# Arduino_car.net
KiCad netlist of a schematic drawn in EAGLE
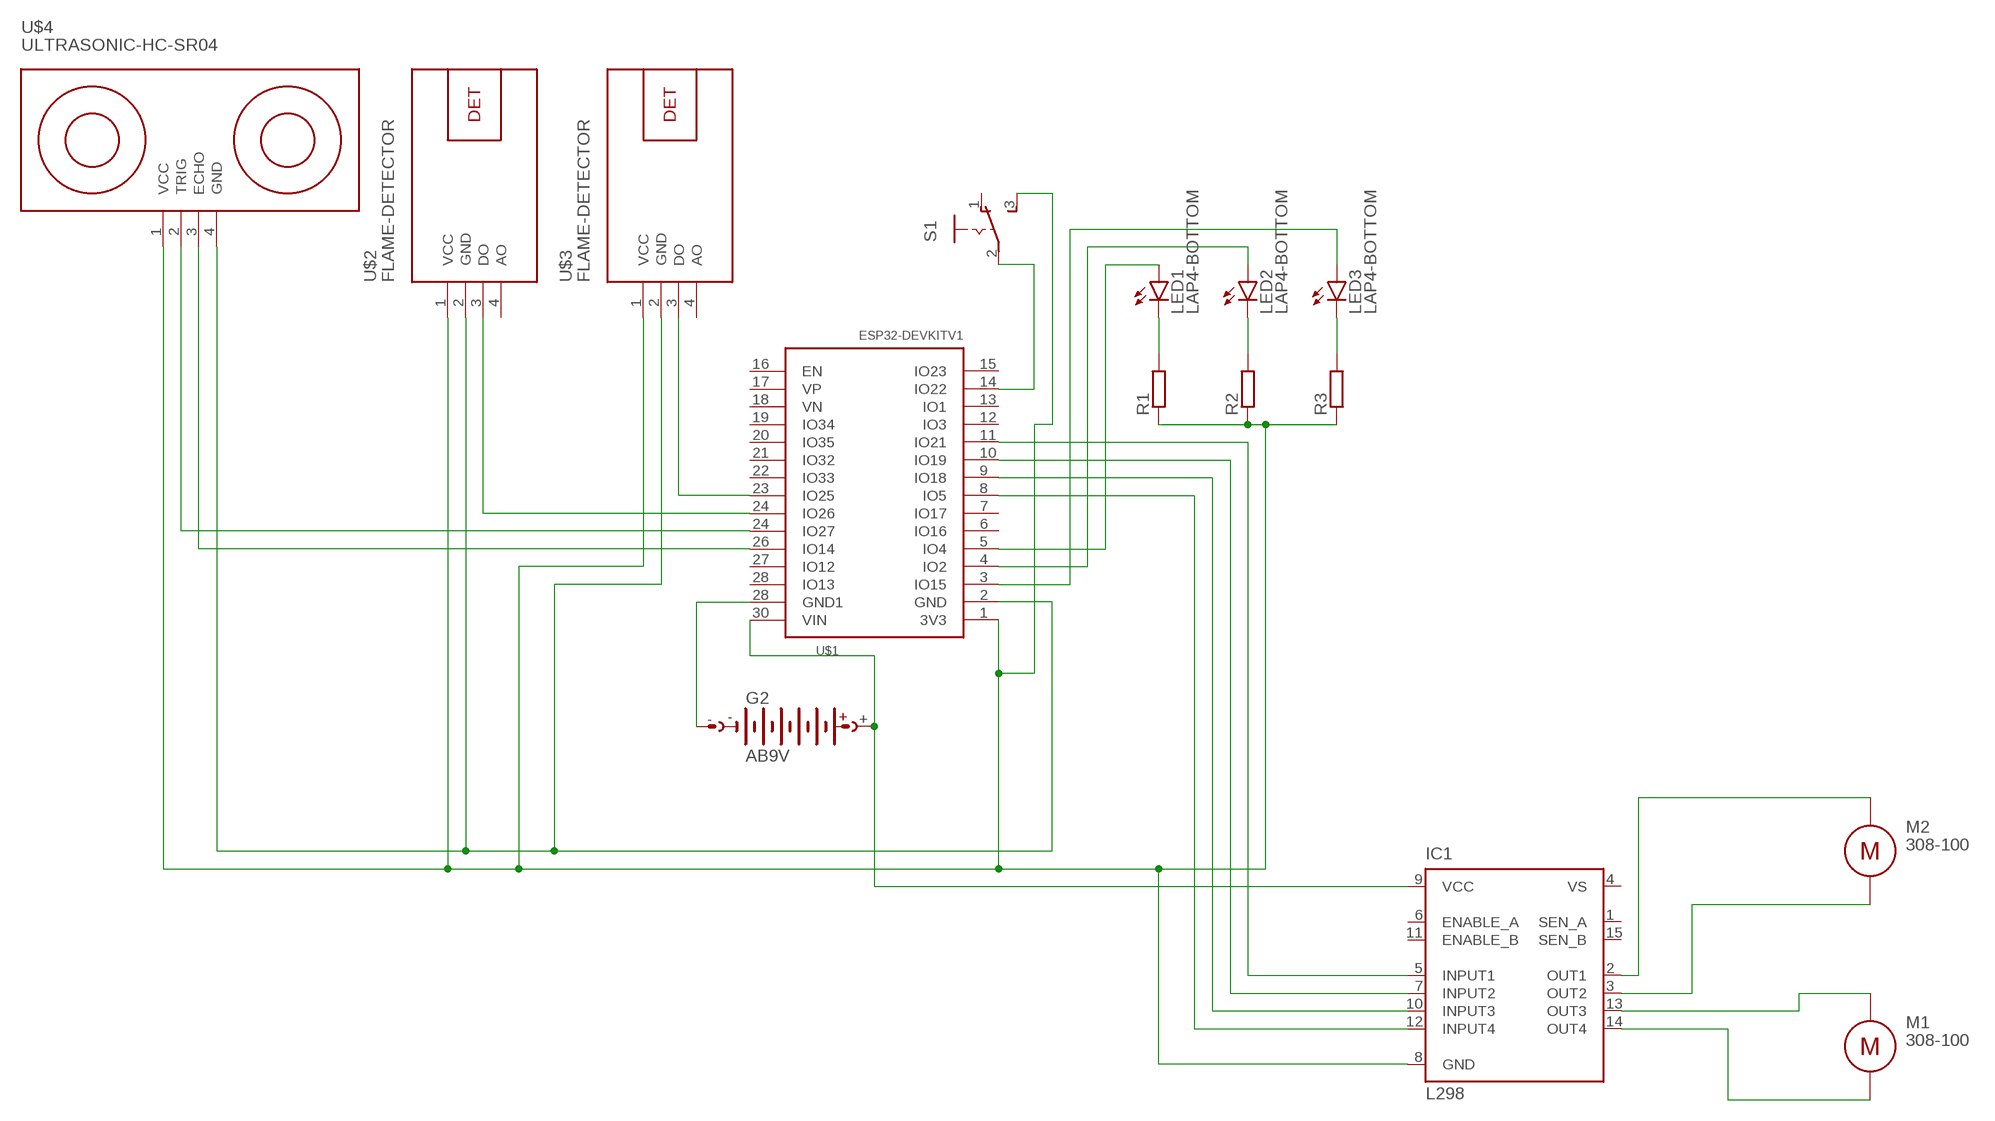
[diagram p0: schematic, sheet 1]

(export (version "E")
  (design (tool "Eeschema 10.0.6"))
  (components
    (comp (ref "G2")
      (value "AB9V")
      (footprint "eagle-import:AB9V")
      (libsource (lib "eagle-import") (part "AB9V"))
    )
    (comp (ref "IC1")
      (value "L298")
      (footprint "eagle-import:MULTIWATT-15")
      (libsource (lib "eagle-import") (part "L298"))
    )
    (comp (ref "LED1")
      (value "LAP4-BOTTOM")
      (footprint "eagle-import:P47F-BOTTOM")
      (libsource (lib "eagle-import") (part "P4-BOTTOMLA"))
    )
    (comp (ref "LED2")
      (value "LAP4-BOTTOM")
      (footprint "eagle-import:P47F-BOTTOM")
      (libsource (lib "eagle-import") (part "P4-BOTTOMLA"))
    )
    (comp (ref "LED3")
      (value "LAP4-BOTTOM")
      (footprint "eagle-import:P47F-BOTTOM")
      (libsource (lib "eagle-import") (part "P4-BOTTOMLA"))
    )
    (comp (ref "M1")
      (value "308-100")
      (footprint "eagle-import:308-100")
      (libsource (lib "eagle-import") (part "308-100"))
    )
    (comp (ref "M2")
      (value "308-100")
      (footprint "eagle-import:308-100")
      (libsource (lib "eagle-import") (part "308-100"))
    )
    (comp (ref "R1")
      (value "BVS")
      (footprint "eagle-import:BVS")
      (libsource (lib "eagle-import") (part "BVS"))
    )
    (comp (ref "R2")
      (value "BVS")
      (footprint "eagle-import:BVS")
      (libsource (lib "eagle-import") (part "BVS"))
    )
    (comp (ref "R3")
      (value "BVS")
      (footprint "eagle-import:BVS")
      (libsource (lib "eagle-import") (part "BVS"))
    )
    (comp (ref "S1")
      (value "255SB")
      (footprint "eagle-import:255SB")
      (libsource (lib "eagle-import") (part "255SB"))
    )
    (comp (ref "U$1")
      (value "ESP32DEVKITV1")
      (footprint "eagle-import:ESP32-DEVKITV1")
      (libsource (lib "eagle-import") (part "ESP32DEVKITV1"))
    )
    (comp (ref "U$2")
      (value "FLAME-DETECTOR")
      (footprint "eagle-import:FLAME-DETECTOR")
      (libsource (lib "eagle-import") (part "FLAME-DETECTOR"))
    )
    (comp (ref "U$3")
      (value "FLAME-DETECTOR")
      (footprint "eagle-import:FLAME-DETECTOR")
      (libsource (lib "eagle-import") (part "FLAME-DETECTOR"))
    )
    (comp (ref "U$4")
      (value "ULTRASONIC-HC-SR04")
      (footprint "eagle-import:ULTRASONIC-HC-SR04")
      (libsource (lib "eagle-import") (part "ULTRASONIC-HC-SR04"))
    )
  )
  (nets
    (net (code "1") (name "/VS") (class "Default")
      (node (ref "IC1") (pin "4") (pinfunction "VS_4") (pintype "power_in"))
    )
    (net (code "2") (name "Net-(IC1-GND)") (class "Default")
      (node (ref "IC1") (pin "8") (pinfunction "GND_8") (pintype "power_in"))
      (node (ref "R1") (pin "2") (pinfunction "2_2") (pintype "passive"))
      (node (ref "R2") (pin "2") (pinfunction "2_2") (pintype "passive"))
      (node (ref "R3") (pin "2") (pinfunction "2_2") (pintype "passive"))
      (node (ref "S1") (pin "3") (pinfunction "S_3") (pintype "passive"))
      (node (ref "U$1") (pin "1") (pinfunction "3V3_1") (pintype "bidirectional"))
      (node (ref "U$2") (pin "1") (pinfunction "VCC_1") (pintype "power_in"))
      (node (ref "U$3") (pin "1") (pinfunction "VCC_1") (pintype "power_in"))
      (node (ref "U$4") (pin "1") (pinfunction "VCC_1") (pintype "power_in"))
    )
    (net (code "3") (name "Net-(IC1-INPUT1)") (class "Default")
      (node (ref "IC1") (pin "5") (pinfunction "INPUT1_5") (pintype "input"))
      (node (ref "U$1") (pin "11") (pinfunction "IO21_11") (pintype "bidirectional"))
    )
    (net (code "4") (name "Net-(IC1-INPUT2)") (class "Default")
      (node (ref "IC1") (pin "7") (pinfunction "INPUT2_7") (pintype "input"))
      (node (ref "U$1") (pin "10") (pinfunction "IO19_10") (pintype "bidirectional"))
    )
    (net (code "5") (name "Net-(IC1-INPUT3)") (class "Default")
      (node (ref "IC1") (pin "10") (pinfunction "INPUT3_10") (pintype "input"))
      (node (ref "U$1") (pin "9") (pinfunction "IO18_9") (pintype "bidirectional"))
    )
    (net (code "6") (name "Net-(IC1-INPUT4)") (class "Default")
      (node (ref "IC1") (pin "12") (pinfunction "INPUT4_12") (pintype "input"))
      (node (ref "U$1") (pin "8") (pinfunction "IO5_8") (pintype "bidirectional"))
    )
    (net (code "7") (name "Net-(IC1-OUT1)") (class "Default")
      (node (ref "IC1") (pin "2") (pinfunction "OUT1_2") (pintype "output"))
      (node (ref "M2") (pin "POS") (pinfunction "POS_POS") (pintype "bidirectional"))
    )
    (net (code "8") (name "Net-(IC1-OUT2)") (class "Default")
      (node (ref "IC1") (pin "3") (pinfunction "OUT2_3") (pintype "output"))
      (node (ref "M2") (pin "NEG") (pinfunction "NEG_NEG") (pintype "bidirectional"))
    )
    (net (code "9") (name "Net-(IC1-OUT3)") (class "Default")
      (node (ref "IC1") (pin "13") (pinfunction "OUT3_13") (pintype "output"))
      (node (ref "M1") (pin "POS") (pinfunction "POS_POS") (pintype "bidirectional"))
    )
    (net (code "10") (name "Net-(IC1-OUT4)") (class "Default")
      (node (ref "IC1") (pin "14") (pinfunction "OUT4_14") (pintype "output"))
      (node (ref "M1") (pin "NEG") (pinfunction "NEG_NEG") (pintype "bidirectional"))
    )
    (net (code "11") (name "Net-(IC1-VCC)") (class "Default")
      (node (ref "G2") (pin "+") (pinfunction "+_+") (pintype "passive"))
      (node (ref "IC1") (pin "9") (pinfunction "VCC_9") (pintype "power_in"))
      (node (ref "U$1") (pin "30") (pinfunction "VIN_30") (pintype "bidirectional"))
    )
    (net (code "12") (name "Net-(LED1-PadC)") (class "Default")
      (node (ref "LED1") (pin "C") (pinfunction "C_C") (pintype "passive"))
      (node (ref "R1") (pin "1") (pinfunction "1_1") (pintype "passive"))
    )
    (net (code "13") (name "Net-(LED2-PadC)") (class "Default")
      (node (ref "LED2") (pin "C") (pinfunction "C_C") (pintype "passive"))
      (node (ref "R2") (pin "1") (pinfunction "1_1") (pintype "passive"))
    )
    (net (code "14") (name "Net-(LED3-PadC)") (class "Default")
      (node (ref "LED3") (pin "C") (pinfunction "C_C") (pintype "passive"))
      (node (ref "R3") (pin "1") (pinfunction "1_1") (pintype "passive"))
    )
    (net (code "15") (name "Net-(S1-P)") (class "Default")
      (node (ref "S1") (pin "2") (pinfunction "P_2") (pintype "passive"))
      (node (ref "U$1") (pin "14") (pinfunction "IO22_14") (pintype "bidirectional"))
    )
    (net (code "16") (name "Net-(U$1-GND)") (class "Default")
      (node (ref "U$1") (pin "2") (pinfunction "GND_2") (pintype "bidirectional"))
      (node (ref "U$2") (pin "2") (pinfunction "GND_2") (pintype "power_in"))
      (node (ref "U$3") (pin "2") (pinfunction "GND_2") (pintype "power_in"))
      (node (ref "U$4") (pin "4") (pinfunction "GND_4") (pintype "power_in"))
    )
    (net (code "17") (name "Net-(U$1-GND1)") (class "Default")
      (node (ref "G2") (pin "-") (pinfunction "-_-") (pintype "passive"))
      (node (ref "U$1") (pin "28") (pinfunction "GND1_28") (pintype "bidirectional"))
    )
    (net (code "18") (name "Net-(U$1-IO2)") (class "Default")
      (node (ref "LED2") (pin "A") (pinfunction "A_A") (pintype "passive"))
      (node (ref "U$1") (pin "4") (pinfunction "IO2_4") (pintype "bidirectional"))
    )
    (net (code "19") (name "Net-(U$1-IO4)") (class "Default")
      (node (ref "LED1") (pin "A") (pinfunction "A_A") (pintype "passive"))
      (node (ref "U$1") (pin "5") (pinfunction "IO4_5") (pintype "bidirectional"))
    )
    (net (code "20") (name "Net-(U$1-IO14)") (class "Default")
      (node (ref "U$1") (pin "26") (pinfunction "IO14_26") (pintype "bidirectional"))
      (node (ref "U$4") (pin "3") (pinfunction "ECHO_3") (pintype "output"))
    )
    (net (code "21") (name "Net-(U$1-IO15)") (class "Default")
      (node (ref "LED3") (pin "A") (pinfunction "A_A") (pintype "passive"))
      (node (ref "U$1") (pin "3") (pinfunction "IO15_3") (pintype "bidirectional"))
    )
    (net (code "22") (name "Net-(U$1-IO25)") (class "Default")
      (node (ref "U$1") (pin "23") (pinfunction "IO25_23") (pintype "bidirectional"))
      (node (ref "U$3") (pin "3") (pinfunction "DO_3") (pintype "bidirectional"))
    )
    (net (code "23") (name "Net-(U$1-IO26)") (class "Default")
      (node (ref "U$1") (pin "24") (pinfunction "IO26_24") (pintype "bidirectional"))
      (node (ref "U$2") (pin "3") (pinfunction "DO_3") (pintype "bidirectional"))
    )
    (net (code "24") (name "Net-(U$1-IO27)") (class "Default")
      (node (ref "U$1") (pin "24") (pinfunction "IO27_24") (pintype "bidirectional"))
      (node (ref "U$4") (pin "2") (pinfunction "TRIG_2") (pintype "input"))
    )
    (net (code "25") (name "unconnected-(IC1-ENABLE_A-Pad6)") (class "Default")
      (node (ref "IC1") (pin "6") (pinfunction "ENABLE_A_6") (pintype "input"))
    )
    (net (code "26") (name "unconnected-(IC1-ENABLE_B-Pad11)") (class "Default")
      (node (ref "IC1") (pin "11") (pinfunction "ENABLE_B_11") (pintype "input"))
    )
    (net (code "27") (name "unconnected-(IC1-SEN_A-Pad1)") (class "Default")
      (node (ref "IC1") (pin "1") (pinfunction "SEN_A_1") (pintype "input"))
    )
    (net (code "28") (name "unconnected-(IC1-SEN_B-Pad15)") (class "Default")
      (node (ref "IC1") (pin "15") (pinfunction "SEN_B_15") (pintype "input"))
    )
    (net (code "29") (name "unconnected-(S1-O-Pad1)") (class "Default")
      (node (ref "S1") (pin "1") (pinfunction "O_1") (pintype "passive"))
    )
    (net (code "30") (name "unconnected-(U$1-EN-Pad16)") (class "Default")
      (node (ref "U$1") (pin "16") (pinfunction "EN_16") (pintype "bidirectional"))
    )
    (net (code "31") (name "unconnected-(U$1-IO1-Pad13)") (class "Default")
      (node (ref "U$1") (pin "13") (pinfunction "IO1_13") (pintype "bidirectional"))
    )
    (net (code "32") (name "unconnected-(U$1-IO3-Pad12)") (class "Default")
      (node (ref "U$1") (pin "12") (pinfunction "IO3_12") (pintype "bidirectional"))
    )
    (net (code "33") (name "unconnected-(U$1-IO12-Pad27)") (class "Default")
      (node (ref "U$1") (pin "27") (pinfunction "IO12_27") (pintype "bidirectional"))
    )
    (net (code "34") (name "unconnected-(U$1-IO13-Pad28)") (class "Default")
      (node (ref "U$1") (pin "28") (pinfunction "IO13_28") (pintype "bidirectional"))
    )
    (net (code "35") (name "unconnected-(U$1-IO16-Pad6)") (class "Default")
      (node (ref "U$1") (pin "6") (pinfunction "IO16_6") (pintype "bidirectional"))
    )
    (net (code "36") (name "unconnected-(U$1-IO17-Pad7)") (class "Default")
      (node (ref "U$1") (pin "7") (pinfunction "IO17_7") (pintype "bidirectional"))
    )
    (net (code "37") (name "unconnected-(U$1-IO23-Pad15)") (class "Default")
      (node (ref "U$1") (pin "15") (pinfunction "IO23_15") (pintype "bidirectional"))
    )
    (net (code "38") (name "unconnected-(U$1-IO32-Pad21)") (class "Default")
      (node (ref "U$1") (pin "21") (pinfunction "IO32_21") (pintype "bidirectional"))
    )
    (net (code "39") (name "unconnected-(U$1-IO33-Pad22)") (class "Default")
      (node (ref "U$1") (pin "22") (pinfunction "IO33_22") (pintype "bidirectional"))
    )
    (net (code "40") (name "unconnected-(U$1-IO34-Pad19)") (class "Default")
      (node (ref "U$1") (pin "19") (pinfunction "IO34_19") (pintype "bidirectional"))
    )
    (net (code "41") (name "unconnected-(U$1-IO35-Pad20)") (class "Default")
      (node (ref "U$1") (pin "20") (pinfunction "IO35_20") (pintype "bidirectional"))
    )
    (net (code "42") (name "unconnected-(U$1-VN-Pad18)") (class "Default")
      (node (ref "U$1") (pin "18") (pinfunction "VN_18") (pintype "bidirectional"))
    )
    (net (code "43") (name "unconnected-(U$1-VP-Pad17)") (class "Default")
      (node (ref "U$1") (pin "17") (pinfunction "VP_17") (pintype "bidirectional"))
    )
    (net (code "44") (name "unconnected-(U$2-AO-Pad4)") (class "Default")
      (node (ref "U$2") (pin "4") (pinfunction "AO_4") (pintype "bidirectional"))
    )
    (net (code "45") (name "unconnected-(U$3-AO-Pad4)") (class "Default")
      (node (ref "U$3") (pin "4") (pinfunction "AO_4") (pintype "bidirectional"))
    )
  )
)
